# 2_unextended_ISO_matrix.net
KiCad netlist of a schematic drawn in Altium Designer
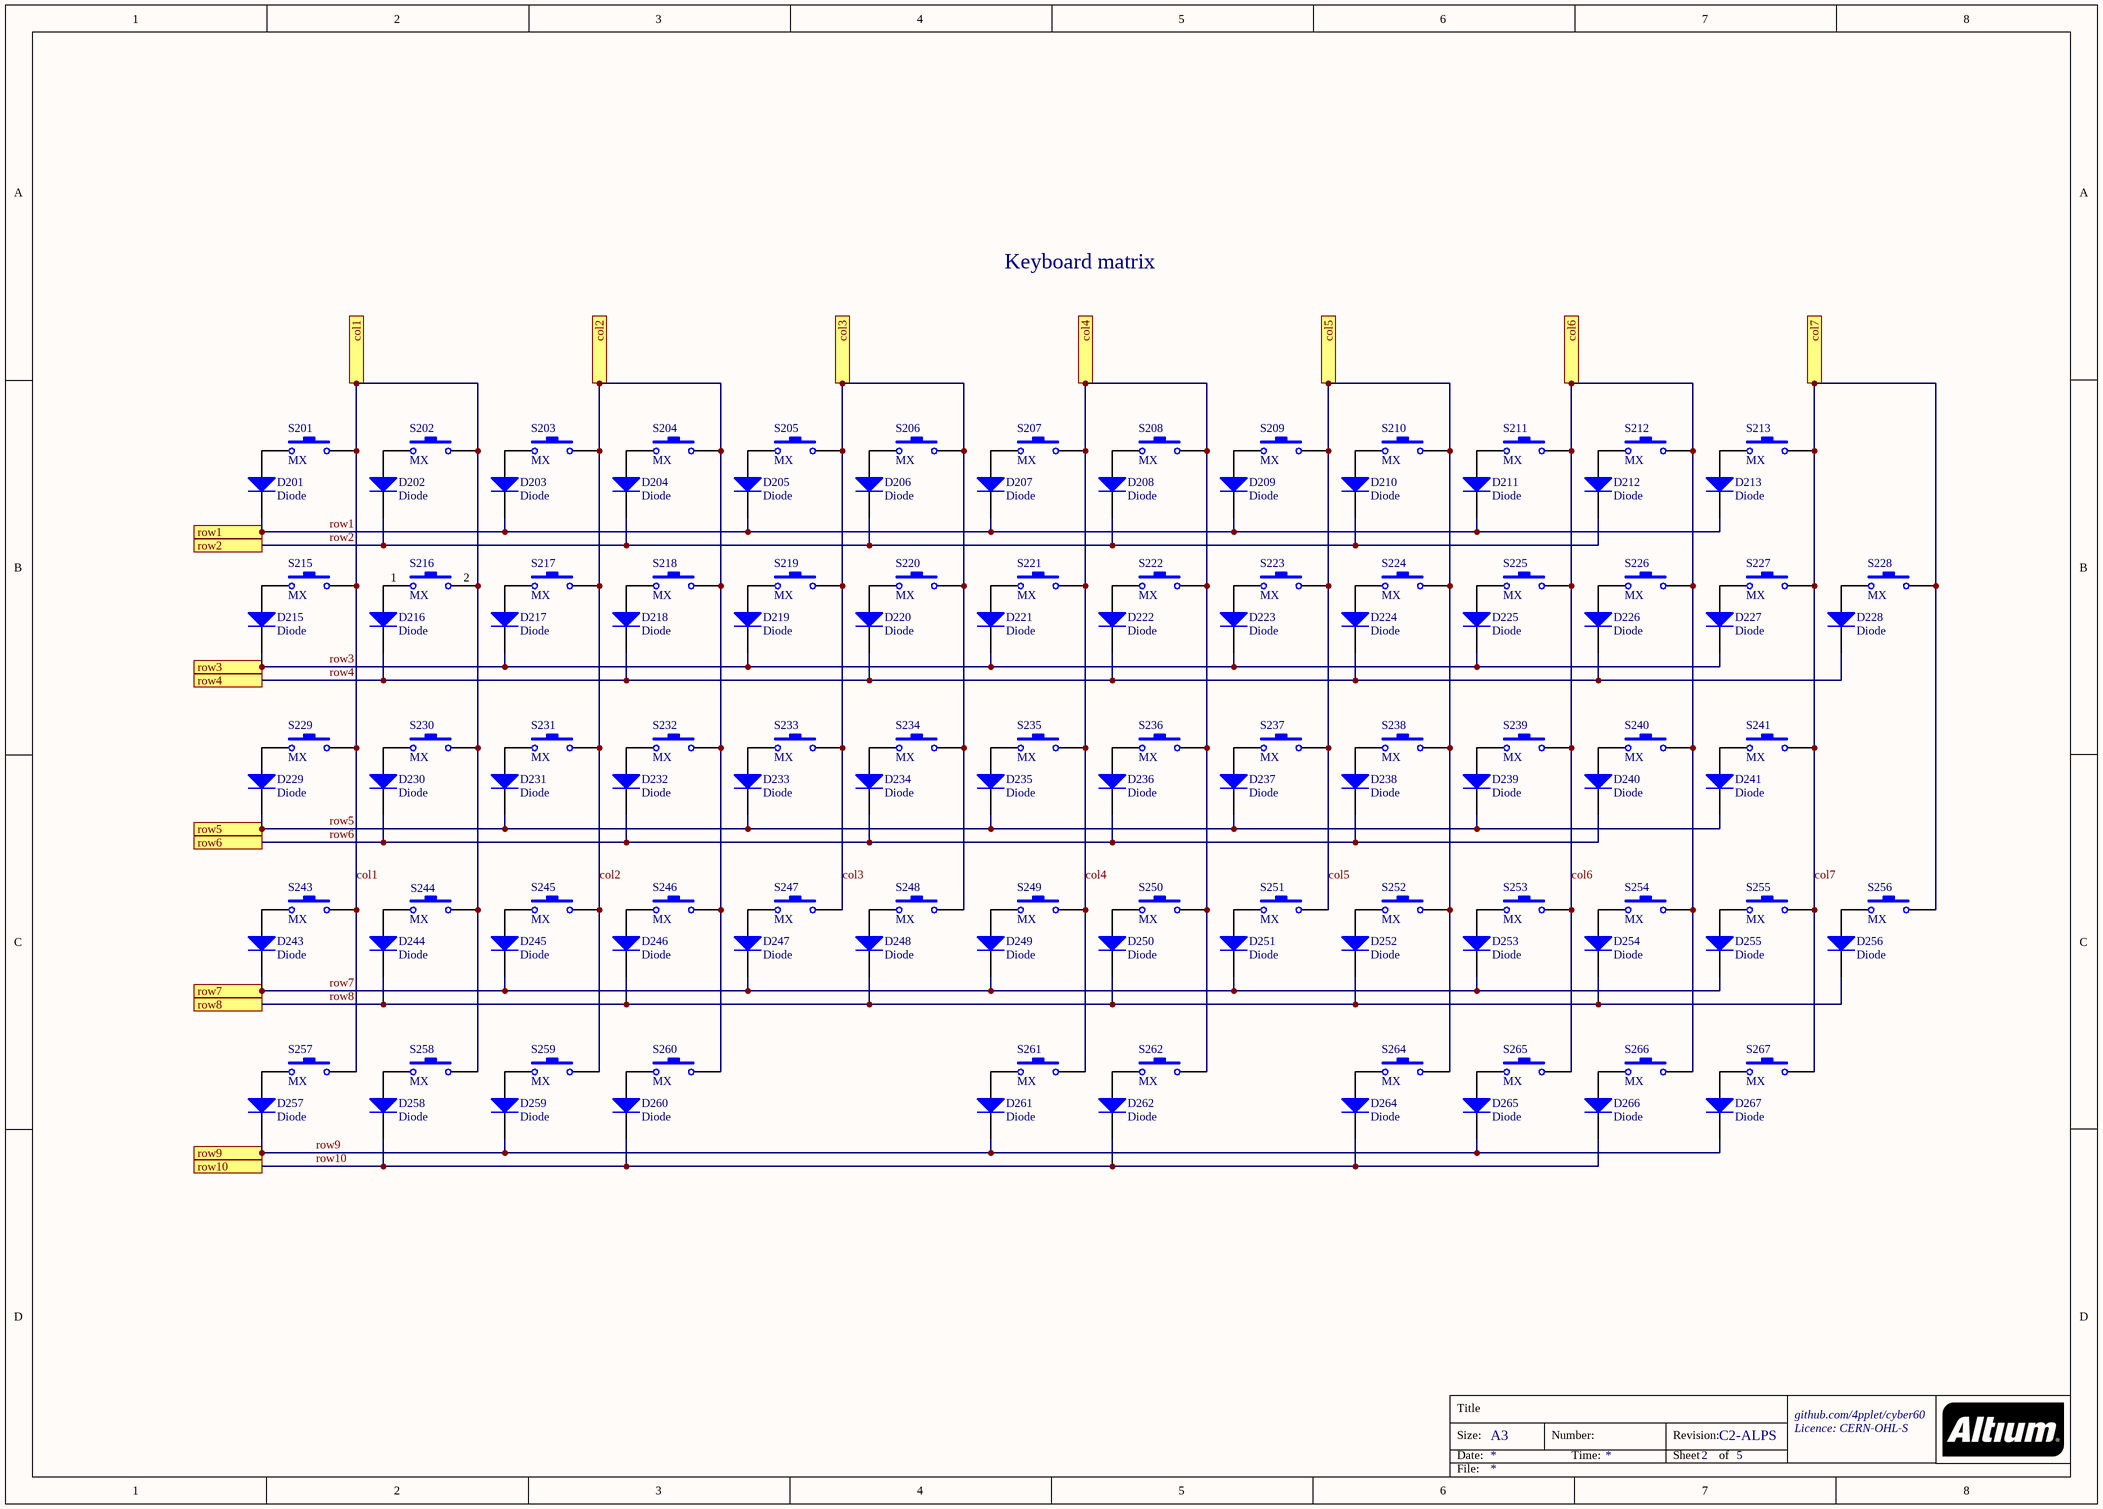
[diagram p0: 2_unextended_ISO_matrix.SchDoc]

(export (version "E")
  (design (tool "Eeschema 10.0.6"))
  (components
    (comp (ref "D201")
      (value "Diode")
      (footprint "SOD-123")
      (description "Default Diode")
      (fields (field (name "LCSC PART #") "C81598") (field (name "MRF.PART") "1N4148W"))
      (libsource (lib "Miscellaneous Devices") (part "Diode"))
    )
    (comp (ref "D202")
      (value "Diode")
      (footprint "SOD-123")
      (description "Default Diode")
      (fields (field (name "LCSC PART #") "C81598") (field (name "MRF.PART") "1N4148W"))
      (libsource (lib "Miscellaneous Devices") (part "Diode"))
    )
    (comp (ref "D203")
      (value "Diode")
      (footprint "SOD-123")
      (description "Default Diode")
      (fields (field (name "LCSC PART #") "C81598") (field (name "MRF.PART") "1N4148W"))
      (libsource (lib "Miscellaneous Devices") (part "Diode"))
    )
    (comp (ref "D204")
      (value "Diode")
      (footprint "SOD-123")
      (description "Default Diode")
      (fields (field (name "LCSC PART #") "C81598") (field (name "MRF.PART") "1N4148W"))
      (libsource (lib "Miscellaneous Devices") (part "Diode"))
    )
    (comp (ref "D205")
      (value "Diode")
      (footprint "SOD-123")
      (description "Default Diode")
      (fields (field (name "LCSC PART #") "C81598") (field (name "MRF.PART") "1N4148W"))
      (libsource (lib "Miscellaneous Devices") (part "Diode"))
    )
    (comp (ref "D206")
      (value "Diode")
      (footprint "SOD-123")
      (description "Default Diode")
      (fields (field (name "LCSC PART #") "C81598") (field (name "MRF.PART") "1N4148W"))
      (libsource (lib "Miscellaneous Devices") (part "Diode"))
    )
    (comp (ref "D207")
      (value "Diode")
      (footprint "SOD-123")
      (description "Default Diode")
      (fields (field (name "LCSC PART #") "C81598") (field (name "MRF.PART") "1N4148W"))
      (libsource (lib "Miscellaneous Devices") (part "Diode"))
    )
    (comp (ref "D208")
      (value "Diode")
      (footprint "SOD-123")
      (description "Default Diode")
      (fields (field (name "LCSC PART #") "C81598") (field (name "MRF.PART") "1N4148W"))
      (libsource (lib "Miscellaneous Devices") (part "Diode"))
    )
    (comp (ref "D209")
      (value "Diode")
      (footprint "SOD-123")
      (description "Default Diode")
      (fields (field (name "LCSC PART #") "C81598") (field (name "MRF.PART") "1N4148W"))
      (libsource (lib "Miscellaneous Devices") (part "Diode"))
    )
    (comp (ref "D210")
      (value "Diode")
      (footprint "SOD-123")
      (description "Default Diode")
      (fields (field (name "LCSC PART #") "C81598") (field (name "MRF.PART") "1N4148W"))
      (libsource (lib "Miscellaneous Devices") (part "Diode"))
    )
    (comp (ref "D211")
      (value "Diode")
      (footprint "SOD-123")
      (description "Default Diode")
      (fields (field (name "LCSC PART #") "C81598") (field (name "MRF.PART") "1N4148W"))
      (libsource (lib "Miscellaneous Devices") (part "Diode"))
    )
    (comp (ref "D212")
      (value "Diode")
      (footprint "SOD-123")
      (description "Default Diode")
      (fields (field (name "LCSC PART #") "C81598") (field (name "MRF.PART") "1N4148W"))
      (libsource (lib "Miscellaneous Devices") (part "Diode"))
    )
    (comp (ref "D213")
      (value "Diode")
      (footprint "SOD-123")
      (description "Default Diode")
      (fields (field (name "LCSC PART #") "C81598") (field (name "MRF.PART") "1N4148W"))
      (libsource (lib "Miscellaneous Devices") (part "Diode"))
    )
    (comp (ref "D215")
      (value "Diode")
      (footprint "SOD-123")
      (description "Default Diode")
      (fields (field (name "LCSC PART #") "C81598") (field (name "MRF.PART") "1N4148W"))
      (libsource (lib "Miscellaneous Devices") (part "Diode"))
    )
    (comp (ref "D216")
      (value "Diode")
      (footprint "SOD-123")
      (description "Default Diode")
      (fields (field (name "LCSC PART #") "C81598") (field (name "MRF.PART") "1N4148W"))
      (libsource (lib "Miscellaneous Devices") (part "Diode"))
    )
    (comp (ref "D217")
      (value "Diode")
      (footprint "SOD-123")
      (description "Default Diode")
      (fields (field (name "LCSC PART #") "C81598") (field (name "MRF.PART") "1N4148W"))
      (libsource (lib "Miscellaneous Devices") (part "Diode"))
    )
    (comp (ref "D218")
      (value "Diode")
      (footprint "SOD-123")
      (description "Default Diode")
      (fields (field (name "LCSC PART #") "C81598") (field (name "MRF.PART") "1N4148W"))
      (libsource (lib "Miscellaneous Devices") (part "Diode"))
    )
    (comp (ref "D219")
      (value "Diode")
      (footprint "SOD-123")
      (description "Default Diode")
      (fields (field (name "LCSC PART #") "C81598") (field (name "MRF.PART") "1N4148W"))
      (libsource (lib "Miscellaneous Devices") (part "Diode"))
    )
    (comp (ref "D220")
      (value "Diode")
      (footprint "SOD-123")
      (description "Default Diode")
      (fields (field (name "LCSC PART #") "C81598") (field (name "MRF.PART") "1N4148W"))
      (libsource (lib "Miscellaneous Devices") (part "Diode"))
    )
    (comp (ref "D221")
      (value "Diode")
      (footprint "SOD-123")
      (description "Default Diode")
      (fields (field (name "LCSC PART #") "C81598") (field (name "MRF.PART") "1N4148W"))
      (libsource (lib "Miscellaneous Devices") (part "Diode"))
    )
    (comp (ref "D222")
      (value "Diode")
      (footprint "SOD-123")
      (description "Default Diode")
      (fields (field (name "LCSC PART #") "C81598") (field (name "MRF.PART") "1N4148W"))
      (libsource (lib "Miscellaneous Devices") (part "Diode"))
    )
    (comp (ref "D223")
      (value "Diode")
      (footprint "SOD-123")
      (description "Default Diode")
      (fields (field (name "LCSC PART #") "C81598") (field (name "MRF.PART") "1N4148W"))
      (libsource (lib "Miscellaneous Devices") (part "Diode"))
    )
    (comp (ref "D224")
      (value "Diode")
      (footprint "SOD-123")
      (description "Default Diode")
      (fields (field (name "LCSC PART #") "C81598") (field (name "MRF.PART") "1N4148W"))
      (libsource (lib "Miscellaneous Devices") (part "Diode"))
    )
    (comp (ref "D225")
      (value "Diode")
      (footprint "SOD-123")
      (description "Default Diode")
      (fields (field (name "LCSC PART #") "C81598") (field (name "MRF.PART") "1N4148W"))
      (libsource (lib "Miscellaneous Devices") (part "Diode"))
    )
    (comp (ref "D226")
      (value "Diode")
      (footprint "SOD-123")
      (description "Default Diode")
      (fields (field (name "LCSC PART #") "C81598") (field (name "MRF.PART") "1N4148W"))
      (libsource (lib "Miscellaneous Devices") (part "Diode"))
    )
    (comp (ref "D227")
      (value "Diode")
      (footprint "SOD-123")
      (description "Default Diode")
      (fields (field (name "LCSC PART #") "C81598") (field (name "MRF.PART") "1N4148W"))
      (libsource (lib "Miscellaneous Devices") (part "Diode"))
    )
    (comp (ref "D228")
      (value "Diode")
      (footprint "SOD-123")
      (description "Default Diode")
      (fields (field (name "LCSC PART #") "C81598") (field (name "MRF.PART") "1N4148W"))
      (libsource (lib "Miscellaneous Devices") (part "Diode"))
    )
    (comp (ref "D229")
      (value "Diode")
      (footprint "SOD-123")
      (description "Default Diode")
      (fields (field (name "LCSC PART #") "C81598") (field (name "MRF.PART") "1N4148W"))
      (libsource (lib "Miscellaneous Devices") (part "Diode"))
    )
    (comp (ref "D230")
      (value "Diode")
      (footprint "SOD-123")
      (description "Default Diode")
      (fields (field (name "LCSC PART #") "C81598") (field (name "MRF.PART") "1N4148W"))
      (libsource (lib "Miscellaneous Devices") (part "Diode"))
    )
    (comp (ref "D231")
      (value "Diode")
      (footprint "SOD-123")
      (description "Default Diode")
      (fields (field (name "LCSC PART #") "C81598") (field (name "MRF.PART") "1N4148W"))
      (libsource (lib "Miscellaneous Devices") (part "Diode"))
    )
    (comp (ref "D232")
      (value "Diode")
      (footprint "SOD-123")
      (description "Default Diode")
      (fields (field (name "LCSC PART #") "C81598") (field (name "MRF.PART") "1N4148W"))
      (libsource (lib "Miscellaneous Devices") (part "Diode"))
    )
    (comp (ref "D233")
      (value "Diode")
      (footprint "SOD-123")
      (description "Default Diode")
      (fields (field (name "LCSC PART #") "C81598") (field (name "MRF.PART") "1N4148W"))
      (libsource (lib "Miscellaneous Devices") (part "Diode"))
    )
    (comp (ref "D234")
      (value "Diode")
      (footprint "SOD-123")
      (description "Default Diode")
      (fields (field (name "LCSC PART #") "C81598") (field (name "MRF.PART") "1N4148W"))
      (libsource (lib "Miscellaneous Devices") (part "Diode"))
    )
    (comp (ref "D235")
      (value "Diode")
      (footprint "SOD-123")
      (description "Default Diode")
      (fields (field (name "LCSC PART #") "C81598") (field (name "MRF.PART") "1N4148W"))
      (libsource (lib "Miscellaneous Devices") (part "Diode"))
    )
    (comp (ref "D236")
      (value "Diode")
      (footprint "SOD-123")
      (description "Default Diode")
      (fields (field (name "LCSC PART #") "C81598") (field (name "MRF.PART") "1N4148W"))
      (libsource (lib "Miscellaneous Devices") (part "Diode"))
    )
    (comp (ref "D237")
      (value "Diode")
      (footprint "SOD-123")
      (description "Default Diode")
      (fields (field (name "LCSC PART #") "C81598") (field (name "MRF.PART") "1N4148W"))
      (libsource (lib "Miscellaneous Devices") (part "Diode"))
    )
    (comp (ref "D238")
      (value "Diode")
      (footprint "SOD-123")
      (description "Default Diode")
      (fields (field (name "LCSC PART #") "C81598") (field (name "MRF.PART") "1N4148W"))
      (libsource (lib "Miscellaneous Devices") (part "Diode"))
    )
    (comp (ref "D239")
      (value "Diode")
      (footprint "SOD-123")
      (description "Default Diode")
      (fields (field (name "LCSC PART #") "C81598") (field (name "MRF.PART") "1N4148W"))
      (libsource (lib "Miscellaneous Devices") (part "Diode"))
    )
    (comp (ref "D240")
      (value "Diode")
      (footprint "SOD-123")
      (description "Default Diode")
      (fields (field (name "LCSC PART #") "C81598") (field (name "MRF.PART") "1N4148W"))
      (libsource (lib "Miscellaneous Devices") (part "Diode"))
    )
    (comp (ref "D241")
      (value "Diode")
      (footprint "SOD-123")
      (description "Default Diode")
      (fields (field (name "LCSC PART #") "C81598") (field (name "MRF.PART") "1N4148W"))
      (libsource (lib "Miscellaneous Devices") (part "Diode"))
    )
    (comp (ref "D243")
      (value "Diode")
      (footprint "SOD-123")
      (description "Default Diode")
      (fields (field (name "LCSC PART #") "C81598") (field (name "MRF.PART") "1N4148W"))
      (libsource (lib "Miscellaneous Devices") (part "Diode"))
    )
    (comp (ref "D244")
      (value "Diode")
      (footprint "SOD-123")
      (description "Default Diode")
      (fields (field (name "LCSC PART #") "C81598") (field (name "MRF.PART") "1N4148W"))
      (libsource (lib "Miscellaneous Devices") (part "Diode"))
    )
    (comp (ref "D245")
      (value "Diode")
      (footprint "SOD-123")
      (description "Default Diode")
      (fields (field (name "LCSC PART #") "C81598") (field (name "MRF.PART") "1N4148W"))
      (libsource (lib "Miscellaneous Devices") (part "Diode"))
    )
    (comp (ref "D246")
      (value "Diode")
      (footprint "SOD-123")
      (description "Default Diode")
      (fields (field (name "LCSC PART #") "C81598") (field (name "MRF.PART") "1N4148W"))
      (libsource (lib "Miscellaneous Devices") (part "Diode"))
    )
    (comp (ref "D247")
      (value "Diode")
      (footprint "SOD-123")
      (description "Default Diode")
      (fields (field (name "LCSC PART #") "C81598") (field (name "MRF.PART") "1N4148W"))
      (libsource (lib "Miscellaneous Devices") (part "Diode"))
    )
    (comp (ref "D248")
      (value "Diode")
      (footprint "SOD-123")
      (description "Default Diode")
      (fields (field (name "LCSC PART #") "C81598") (field (name "MRF.PART") "1N4148W"))
      (libsource (lib "Miscellaneous Devices") (part "Diode"))
    )
    (comp (ref "D249")
      (value "Diode")
      (footprint "SOD-123")
      (description "Default Diode")
      (fields (field (name "LCSC PART #") "C81598") (field (name "MRF.PART") "1N4148W"))
      (libsource (lib "Miscellaneous Devices") (part "Diode"))
    )
    (comp (ref "D250")
      (value "Diode")
      (footprint "SOD-123")
      (description "Default Diode")
      (fields (field (name "LCSC PART #") "C81598") (field (name "MRF.PART") "1N4148W"))
      (libsource (lib "Miscellaneous Devices") (part "Diode"))
    )
    (comp (ref "D251")
      (value "Diode")
      (footprint "SOD-123")
      (description "Default Diode")
      (fields (field (name "LCSC PART #") "C81598") (field (name "MRF.PART") "1N4148W"))
      (libsource (lib "Miscellaneous Devices") (part "Diode"))
    )
    (comp (ref "D252")
      (value "Diode")
      (footprint "SOD-123")
      (description "Default Diode")
      (fields (field (name "LCSC PART #") "C81598") (field (name "MRF.PART") "1N4148W"))
      (libsource (lib "Miscellaneous Devices") (part "Diode"))
    )
    (comp (ref "D253")
      (value "Diode")
      (footprint "SOD-123")
      (description "Default Diode")
      (fields (field (name "LCSC PART #") "C81598") (field (name "MRF.PART") "1N4148W"))
      (libsource (lib "Miscellaneous Devices") (part "Diode"))
    )
    (comp (ref "D254")
      (value "Diode")
      (footprint "SOD-123")
      (description "Default Diode")
      (fields (field (name "LCSC PART #") "C81598") (field (name "MRF.PART") "1N4148W"))
      (libsource (lib "Miscellaneous Devices") (part "Diode"))
    )
    (comp (ref "D255")
      (value "Diode")
      (footprint "SOD-123")
      (description "Default Diode")
      (fields (field (name "LCSC PART #") "C81598") (field (name "MRF.PART") "1N4148W"))
      (libsource (lib "Miscellaneous Devices") (part "Diode"))
    )
    (comp (ref "D256")
      (value "Diode")
      (footprint "SOD-123")
      (description "Default Diode")
      (fields (field (name "LCSC PART #") "C81598") (field (name "MRF.PART") "1N4148W"))
      (libsource (lib "Miscellaneous Devices") (part "Diode"))
    )
    (comp (ref "D257")
      (value "Diode")
      (footprint "SOD-123")
      (description "Default Diode")
      (fields (field (name "LCSC PART #") "C81598") (field (name "MRF.PART") "1N4148W"))
      (libsource (lib "Miscellaneous Devices") (part "Diode"))
    )
    (comp (ref "D258")
      (value "Diode")
      (footprint "SOD-123")
      (description "Default Diode")
      (fields (field (name "LCSC PART #") "C81598") (field (name "MRF.PART") "1N4148W"))
      (libsource (lib "Miscellaneous Devices") (part "Diode"))
    )
    (comp (ref "D259")
      (value "Diode")
      (footprint "SOD-123")
      (description "Default Diode")
      (fields (field (name "LCSC PART #") "C81598") (field (name "MRF.PART") "1N4148W"))
      (libsource (lib "Miscellaneous Devices") (part "Diode"))
    )
    (comp (ref "D260")
      (value "Diode")
      (footprint "SOD-123")
      (description "Default Diode")
      (fields (field (name "LCSC PART #") "C81598") (field (name "MRF.PART") "1N4148W"))
      (libsource (lib "Miscellaneous Devices") (part "Diode"))
    )
    (comp (ref "D261")
      (value "Diode")
      (footprint "SOD-123")
      (description "Default Diode")
      (fields (field (name "LCSC PART #") "C81598") (field (name "MRF.PART") "1N4148W"))
      (libsource (lib "Miscellaneous Devices") (part "Diode"))
    )
    (comp (ref "D262")
      (value "Diode")
      (footprint "SOD-123")
      (description "Default Diode")
      (fields (field (name "LCSC PART #") "C81598") (field (name "MRF.PART") "1N4148W"))
      (libsource (lib "Miscellaneous Devices") (part "Diode"))
    )
    (comp (ref "D264")
      (value "Diode")
      (footprint "SOD-123")
      (description "Default Diode")
      (fields (field (name "LCSC PART #") "C81598") (field (name "MRF.PART") "1N4148W"))
      (libsource (lib "Miscellaneous Devices") (part "Diode"))
    )
    (comp (ref "D265")
      (value "Diode")
      (footprint "SOD-123")
      (description "Default Diode")
      (fields (field (name "LCSC PART #") "C81598") (field (name "MRF.PART") "1N4148W"))
      (libsource (lib "Miscellaneous Devices") (part "Diode"))
    )
    (comp (ref "D266")
      (value "Diode")
      (footprint "SOD-123")
      (description "Default Diode")
      (fields (field (name "LCSC PART #") "C81598") (field (name "MRF.PART") "1N4148W"))
      (libsource (lib "Miscellaneous Devices") (part "Diode"))
    )
    (comp (ref "D267")
      (value "Diode")
      (footprint "SOD-123")
      (description "Default Diode")
      (fields (field (name "LCSC PART #") "C81598") (field (name "MRF.PART") "1N4148W"))
      (libsource (lib "Miscellaneous Devices") (part "Diode"))
    )
    (comp (ref "S201")
      (value "MX")
      (footprint "Alps-switch - switched pol")
      (description "Switch")
      (libsource (lib "Miscellaneous Devices") (part "SW-PB"))
    )
    (comp (ref "S202")
      (value "MX")
      (footprint "Alps-switch - switched pol")
      (description "Switch")
      (libsource (lib "Miscellaneous Devices") (part "SW-PB"))
    )
    (comp (ref "S203")
      (value "MX")
      (footprint "Alps-switch - switched pol")
      (description "Switch")
      (libsource (lib "Miscellaneous Devices") (part "SW-PB"))
    )
    (comp (ref "S204")
      (value "MX")
      (footprint "Alps-switch - switched pol")
      (description "Switch")
      (libsource (lib "Miscellaneous Devices") (part "SW-PB"))
    )
    (comp (ref "S205")
      (value "MX")
      (footprint "Alps-switch - switched pol")
      (description "Switch")
      (libsource (lib "Miscellaneous Devices") (part "SW-PB"))
    )
    (comp (ref "S206")
      (value "MX")
      (footprint "Alps-switch - switched pol")
      (description "Switch")
      (libsource (lib "Miscellaneous Devices") (part "SW-PB"))
    )
    (comp (ref "S207")
      (value "MX")
      (footprint "Alps-switch - switched pol")
      (description "Switch")
      (libsource (lib "Miscellaneous Devices") (part "SW-PB"))
    )
    (comp (ref "S208")
      (value "MX")
      (footprint "Alps-switch - switched pol")
      (description "Switch")
      (libsource (lib "Miscellaneous Devices") (part "SW-PB"))
    )
    (comp (ref "S209")
      (value "MX")
      (footprint "Alps-switch - switched pol")
      (description "Switch")
      (libsource (lib "Miscellaneous Devices") (part "SW-PB"))
    )
    (comp (ref "S210")
      (value "MX")
      (footprint "Alps-switch - switched pol")
      (description "Switch")
      (libsource (lib "Miscellaneous Devices") (part "SW-PB"))
    )
    (comp (ref "S211")
      (value "MX")
      (footprint "Alps-switch - switched pol")
      (description "Switch")
      (libsource (lib "Miscellaneous Devices") (part "SW-PB"))
    )
    (comp (ref "S212")
      (value "MX")
      (footprint "Alps-switch - switched pol")
      (description "Switch")
      (libsource (lib "Miscellaneous Devices") (part "SW-PB"))
    )
    (comp (ref "S213")
      (value "MX")
      (footprint "Alps-switch")
      (description "Switch")
      (libsource (lib "Miscellaneous Devices") (part "SW-PB"))
    )
    (comp (ref "S215")
      (value "MX")
      (footprint "Alps-switch - switched pol")
      (description "TAB")
      (libsource (lib "Miscellaneous Devices") (part "SW-PB"))
    )
    (comp (ref "S216")
      (value "MX")
      (footprint "Alps-switch - switched pol")
      (description "Switch")
      (libsource (lib "") (part "SW-PB_1"))
    )
    (comp (ref "S217")
      (value "MX")
      (footprint "Alps-switch - switched pol")
      (description "Switch")
      (libsource (lib "Miscellaneous Devices") (part "SW-PB"))
    )
    (comp (ref "S218")
      (value "MX")
      (footprint "Alps-switch - switched pol")
      (description "Switch")
      (libsource (lib "Miscellaneous Devices") (part "SW-PB"))
    )
    (comp (ref "S219")
      (value "MX")
      (footprint "Alps-switch - switched pol")
      (description "Switch")
      (libsource (lib "Miscellaneous Devices") (part "SW-PB"))
    )
    (comp (ref "S220")
      (value "MX")
      (footprint "Alps-switch - switched pol")
      (description "Switch")
      (libsource (lib "Miscellaneous Devices") (part "SW-PB"))
    )
    (comp (ref "S221")
      (value "MX")
      (footprint "Alps-switch - switched pol")
      (description "Switch")
      (libsource (lib "Miscellaneous Devices") (part "SW-PB"))
    )
    (comp (ref "S222")
      (value "MX")
      (footprint "Alps-switch - switched pol")
      (description "Switch")
      (libsource (lib "Miscellaneous Devices") (part "SW-PB"))
    )
    (comp (ref "S223")
      (value "MX")
      (footprint "Alps-switch - switched pol")
      (description "Switch")
      (libsource (lib "Miscellaneous Devices") (part "SW-PB"))
    )
    (comp (ref "S224")
      (value "MX")
      (footprint "Alps-switch - switched pol")
      (description "Switch")
      (libsource (lib "Miscellaneous Devices") (part "SW-PB"))
    )
    (comp (ref "S225")
      (value "MX")
      (footprint "Alps-switch - switched pol")
      (description "Switch")
      (libsource (lib "Miscellaneous Devices") (part "SW-PB"))
    )
    (comp (ref "S226")
      (value "MX")
      (footprint "Alps-switch")
      (description "Switch")
      (libsource (lib "Miscellaneous Devices") (part "SW-PB"))
    )
    (comp (ref "S227")
      (value "MX")
      (footprint "Alps-switch")
      (description "Switch")
      (libsource (lib "Miscellaneous Devices") (part "SW-PB"))
    )
    (comp (ref "S228")
      (value "MX")
      (footprint "Alps-switch - switched pol")
      (description "Switch")
      (libsource (lib "Miscellaneous Devices") (part "SW-PB"))
    )
    (comp (ref "S229")
      (value "MX")
      (footprint "Alps-switch")
      (description "Switch")
      (libsource (lib "Miscellaneous Devices") (part "SW-PB"))
    )
    (comp (ref "S230")
      (value "MX")
      (footprint "Alps-switch - switched pol")
      (description "Switch")
      (libsource (lib "Miscellaneous Devices") (part "SW-PB"))
    )
    (comp (ref "S231")
      (value "MX")
      (footprint "Alps-switch - switched pol")
      (description "Switch")
      (libsource (lib "Miscellaneous Devices") (part "SW-PB"))
    )
    (comp (ref "S232")
      (value "MX")
      (footprint "Alps-switch - switched pol")
      (description "Switch")
      (libsource (lib "Miscellaneous Devices") (part "SW-PB"))
    )
    (comp (ref "S233")
      (value "MX")
      (footprint "Alps-switch - switched pol")
      (description "Switch")
      (libsource (lib "Miscellaneous Devices") (part "SW-PB"))
    )
    (comp (ref "S234")
      (value "MX")
      (footprint "Alps-switch - switched pol")
      (description "Switch")
      (libsource (lib "Miscellaneous Devices") (part "SW-PB"))
    )
    (comp (ref "S235")
      (value "MX")
      (footprint "Alps-switch - switched pol")
      (description "Switch")
      (libsource (lib "Miscellaneous Devices") (part "SW-PB"))
    )
    (comp (ref "S236")
      (value "MX")
      (footprint "Alps-switch - switched pol")
      (description "Switch")
      (libsource (lib "Miscellaneous Devices") (part "SW-PB"))
    )
    (comp (ref "S237")
      (value "MX")
      (footprint "Alps-switch - switched pol")
      (description "Switch")
      (libsource (lib "Miscellaneous Devices") (part "SW-PB"))
    )
    (comp (ref "S238")
      (value "MX")
      (footprint "Alps-switch - switched pol")
      (description "Switch")
      (libsource (lib "Miscellaneous Devices") (part "SW-PB"))
    )
    (comp (ref "S239")
      (value "MX")
      (footprint "Alps-switch")
      (description "Switch")
      (libsource (lib "Miscellaneous Devices") (part "SW-PB"))
    )
    (comp (ref "S240")
      (value "MX")
      (footprint "Alps-switch - switched pol")
      (description "Switch")
      (libsource (lib "Miscellaneous Devices") (part "SW-PB"))
    )
    (comp (ref "S241")
      (value "MX")
      (footprint "Alps-switch - switched pol")
      (description "Switch")
      (libsource (lib "Miscellaneous Devices") (part "SW-PB"))
    )
    (comp (ref "S243")
      (value "MX")
      (footprint "Alps-switch - switched pol")
      (description "Switch")
      (libsource (lib "Miscellaneous Devices") (part "SW-PB"))
    )
    (comp (ref "S244")
      (value "MX")
      (footprint "Alps-switch - switched pol")
      (description "Switch")
      (libsource (lib "Miscellaneous Devices") (part "SW-PB"))
    )
    (comp (ref "S245")
      (value "MX")
      (footprint "Alps-switch - switched pol")
      (description "Switch")
      (libsource (lib "Miscellaneous Devices") (part "SW-PB"))
    )
    (comp (ref "S246")
      (value "MX")
      (footprint "Alps-switch - switched pol")
      (description "Switch")
      (libsource (lib "Miscellaneous Devices") (part "SW-PB"))
    )
    (comp (ref "S247")
      (value "MX")
      (footprint "Alps-switch - switched pol")
      (description "Switch")
      (libsource (lib "Miscellaneous Devices") (part "SW-PB"))
    )
    (comp (ref "S248")
      (value "MX")
      (footprint "Alps-switch - switched pol")
      (description "Switch")
      (libsource (lib "Miscellaneous Devices") (part "SW-PB"))
    )
    (comp (ref "S249")
      (value "MX")
      (footprint "Alps-switch - switched pol")
      (description "Switch")
      (libsource (lib "Miscellaneous Devices") (part "SW-PB"))
    )
    (comp (ref "S250")
      (value "MX")
      (footprint "Alps-switch - switched pol")
      (description "Switch")
      (libsource (lib "Miscellaneous Devices") (part "SW-PB"))
    )
    (comp (ref "S251")
      (value "MX")
      (footprint "Alps-switch - switched pol")
      (description "Switch")
      (libsource (lib "Miscellaneous Devices") (part "SW-PB"))
    )
    (comp (ref "S252")
      (value "MX")
      (footprint "Alps-switch - switched pol")
      (description "Switch")
      (libsource (lib "Miscellaneous Devices") (part "SW-PB"))
    )
    (comp (ref "S253")
      (value "MX")
      (footprint "Alps-switch - switched pol")
      (description "Switch")
      (libsource (lib "Miscellaneous Devices") (part "SW-PB"))
    )
    (comp (ref "S254")
      (value "MX")
      (footprint "Alps-switch - switched pol")
      (description "Switch")
      (libsource (lib "Miscellaneous Devices") (part "SW-PB"))
    )
    (comp (ref "S255")
      (value "MX")
      (footprint "Alps-switch")
      (description "Switch")
      (libsource (lib "Miscellaneous Devices") (part "SW-PB"))
    )
    (comp (ref "S256")
      (value "MX")
      (footprint "Alps-switch")
      (description "Switch")
      (libsource (lib "Miscellaneous Devices") (part "SW-PB"))
    )
    (comp (ref "S257")
      (value "MX")
      (footprint "Alps-switch - switched pol")
      (description "Switch")
      (libsource (lib "Miscellaneous Devices") (part "SW-PB"))
    )
    (comp (ref "S258")
      (value "MX")
      (footprint "Alps-switch")
      (description "Switch")
      (libsource (lib "Miscellaneous Devices") (part "SW-PB"))
    )
    (comp (ref "S259")
      (value "MX")
      (footprint "Alps-switch")
      (description "Switch")
      (libsource (lib "Miscellaneous Devices") (part "SW-PB"))
    )
    (comp (ref "S260")
      (value "MX")
      (footprint "Alps-switch")
      (description "Switch")
      (libsource (lib "Miscellaneous Devices") (part "SW-PB"))
    )
    (comp (ref "S261")
      (value "MX")
      (footprint "Alps-switch - switched pol")
      (description "Switch")
      (libsource (lib "Miscellaneous Devices") (part "SW-PB"))
    )
    (comp (ref "S262")
      (value "MX")
      (footprint "Alps-switch - switched pol")
      (description "Switch")
      (libsource (lib "Miscellaneous Devices") (part "SW-PB"))
    )
    (comp (ref "S264")
      (value "MX")
      (footprint "Alps-switch")
      (description "Switch")
      (libsource (lib "Miscellaneous Devices") (part "SW-PB"))
    )
    (comp (ref "S265")
      (value "MX")
      (footprint "Alps-switch")
      (description "Switch")
      (libsource (lib "Miscellaneous Devices") (part "SW-PB"))
    )
    (comp (ref "S266")
      (value "MX")
      (footprint "Alps-switch")
      (description "Switch")
      (libsource (lib "Miscellaneous Devices") (part "SW-PB"))
    )
    (comp (ref "S267")
      (value "MX")
      (footprint "ALPS-switch - AEKISO r_shift")
      (description "Switch")
      (libsource (lib "Miscellaneous Devices") (part "SW-PB"))
    )
  )
  (nets
    (net (code "1") (name "/col1") (class "Default")
      (node (ref "S201") (pin "2") (pinfunction "2_2") (pintype "passive"))
      (node (ref "S202") (pin "2") (pinfunction "2_2") (pintype "passive"))
      (node (ref "S215") (pin "2") (pinfunction "2_2") (pintype "passive"))
      (node (ref "S216") (pin "2") (pinfunction "2_2") (pintype "passive"))
      (node (ref "S229") (pin "2") (pinfunction "2_2") (pintype "passive"))
      (node (ref "S230") (pin "2") (pinfunction "2_2") (pintype "passive"))
      (node (ref "S243") (pin "2") (pinfunction "2_2") (pintype "passive"))
      (node (ref "S244") (pin "2") (pinfunction "2_2") (pintype "passive"))
      (node (ref "S257") (pin "2") (pinfunction "2_2") (pintype "passive"))
      (node (ref "S258") (pin "2") (pinfunction "2_2") (pintype "passive"))
    )
    (net (code "2") (name "/col2") (class "Default")
      (node (ref "S203") (pin "2") (pinfunction "2_2") (pintype "passive"))
      (node (ref "S204") (pin "2") (pinfunction "2_2") (pintype "passive"))
      (node (ref "S217") (pin "2") (pinfunction "2_2") (pintype "passive"))
      (node (ref "S218") (pin "2") (pinfunction "2_2") (pintype "passive"))
      (node (ref "S231") (pin "2") (pinfunction "2_2") (pintype "passive"))
      (node (ref "S232") (pin "2") (pinfunction "2_2") (pintype "passive"))
      (node (ref "S245") (pin "2") (pinfunction "2_2") (pintype "passive"))
      (node (ref "S246") (pin "2") (pinfunction "2_2") (pintype "passive"))
      (node (ref "S259") (pin "2") (pinfunction "2_2") (pintype "passive"))
      (node (ref "S260") (pin "2") (pinfunction "2_2") (pintype "passive"))
    )
    (net (code "3") (name "/col3") (class "Default")
      (node (ref "S205") (pin "2") (pinfunction "2_2") (pintype "passive"))
      (node (ref "S206") (pin "2") (pinfunction "2_2") (pintype "passive"))
      (node (ref "S219") (pin "2") (pinfunction "2_2") (pintype "passive"))
      (node (ref "S220") (pin "2") (pinfunction "2_2") (pintype "passive"))
      (node (ref "S233") (pin "2") (pinfunction "2_2") (pintype "passive"))
      (node (ref "S234") (pin "2") (pinfunction "2_2") (pintype "passive"))
      (node (ref "S247") (pin "2") (pinfunction "2_2") (pintype "passive"))
      (node (ref "S248") (pin "2") (pinfunction "2_2") (pintype "passive"))
    )
    (net (code "4") (name "/col4") (class "Default")
      (node (ref "S207") (pin "2") (pinfunction "2_2") (pintype "passive"))
      (node (ref "S208") (pin "2") (pinfunction "2_2") (pintype "passive"))
      (node (ref "S221") (pin "2") (pinfunction "2_2") (pintype "passive"))
      (node (ref "S222") (pin "2") (pinfunction "2_2") (pintype "passive"))
      (node (ref "S235") (pin "2") (pinfunction "2_2") (pintype "passive"))
      (node (ref "S236") (pin "2") (pinfunction "2_2") (pintype "passive"))
      (node (ref "S249") (pin "2") (pinfunction "2_2") (pintype "passive"))
      (node (ref "S250") (pin "2") (pinfunction "2_2") (pintype "passive"))
      (node (ref "S261") (pin "1") (pinfunction "1_1") (pintype "passive"))
      (node (ref "S262") (pin "2") (pinfunction "2_2") (pintype "passive"))
    )
    (net (code "5") (name "/col5") (class "Default")
      (node (ref "S209") (pin "2") (pinfunction "2_2") (pintype "passive"))
      (node (ref "S210") (pin "2") (pinfunction "2_2") (pintype "passive"))
      (node (ref "S223") (pin "2") (pinfunction "2_2") (pintype "passive"))
      (node (ref "S224") (pin "2") (pinfunction "2_2") (pintype "passive"))
      (node (ref "S237") (pin "2") (pinfunction "2_2") (pintype "passive"))
      (node (ref "S238") (pin "2") (pinfunction "2_2") (pintype "passive"))
      (node (ref "S251") (pin "2") (pinfunction "2_2") (pintype "passive"))
      (node (ref "S252") (pin "2") (pinfunction "2_2") (pintype "passive"))
      (node (ref "S264") (pin "1") (pinfunction "1_1") (pintype "passive"))
    )
    (net (code "6") (name "/col6") (class "Default")
      (node (ref "S211") (pin "2") (pinfunction "2_2") (pintype "passive"))
      (node (ref "S212") (pin "2") (pinfunction "2_2") (pintype "passive"))
      (node (ref "S225") (pin "2") (pinfunction "2_2") (pintype "passive"))
      (node (ref "S226") (pin "2") (pinfunction "2_2") (pintype "passive"))
      (node (ref "S239") (pin "2") (pinfunction "2_2") (pintype "passive"))
      (node (ref "S240") (pin "2") (pinfunction "2_2") (pintype "passive"))
      (node (ref "S253") (pin "2") (pinfunction "2_2") (pintype "passive"))
      (node (ref "S254") (pin "2") (pinfunction "2_2") (pintype "passive"))
      (node (ref "S265") (pin "2") (pinfunction "2_2") (pintype "passive"))
      (node (ref "S266") (pin "2") (pinfunction "2_2") (pintype "passive"))
    )
    (net (code "7") (name "/col7") (class "Default")
      (node (ref "S213") (pin "2") (pinfunction "2_2") (pintype "passive"))
      (node (ref "S227") (pin "2") (pinfunction "2_2") (pintype "passive"))
      (node (ref "S228") (pin "1") (pinfunction "1_1") (pintype "passive"))
      (node (ref "S241") (pin "2") (pinfunction "2_2") (pintype "passive"))
      (node (ref "S255") (pin "2") (pinfunction "2_2") (pintype "passive"))
      (node (ref "S256") (pin "2") (pinfunction "2_2") (pintype "passive"))
      (node (ref "S267") (pin "1") (pinfunction "1_1") (pintype "passive"))
    )
    (net (code "8") (name "/row1") (class "Default")
      (node (ref "D201") (pin "2") (pinfunction "K_2") (pintype "passive"))
      (node (ref "D203") (pin "2") (pinfunction "K_2") (pintype "passive"))
      (node (ref "D205") (pin "2") (pinfunction "K_2") (pintype "passive"))
      (node (ref "D207") (pin "2") (pinfunction "K_2") (pintype "passive"))
      (node (ref "D209") (pin "2") (pinfunction "K_2") (pintype "passive"))
      (node (ref "D211") (pin "2") (pinfunction "K_2") (pintype "passive"))
      (node (ref "D213") (pin "2") (pinfunction "K_2") (pintype "passive"))
    )
    (net (code "9") (name "/row2") (class "Default")
      (node (ref "D202") (pin "2") (pinfunction "K_2") (pintype "passive"))
      (node (ref "D204") (pin "2") (pinfunction "K_2") (pintype "passive"))
      (node (ref "D206") (pin "2") (pinfunction "K_2") (pintype "passive"))
      (node (ref "D208") (pin "2") (pinfunction "K_2") (pintype "passive"))
      (node (ref "D210") (pin "2") (pinfunction "K_2") (pintype "passive"))
      (node (ref "D212") (pin "2") (pinfunction "K_2") (pintype "passive"))
    )
    (net (code "10") (name "/row3") (class "Default")
      (node (ref "D215") (pin "2") (pinfunction "K_2") (pintype "passive"))
      (node (ref "D217") (pin "2") (pinfunction "K_2") (pintype "passive"))
      (node (ref "D219") (pin "2") (pinfunction "K_2") (pintype "passive"))
      (node (ref "D221") (pin "2") (pinfunction "K_2") (pintype "passive"))
      (node (ref "D223") (pin "2") (pinfunction "K_2") (pintype "passive"))
      (node (ref "D225") (pin "2") (pinfunction "K_2") (pintype "passive"))
      (node (ref "D227") (pin "2") (pinfunction "K_2") (pintype "passive"))
    )
    (net (code "11") (name "/row4") (class "Default")
      (node (ref "D216") (pin "2") (pinfunction "K_2") (pintype "passive"))
      (node (ref "D218") (pin "2") (pinfunction "K_2") (pintype "passive"))
      (node (ref "D220") (pin "2") (pinfunction "K_2") (pintype "passive"))
      (node (ref "D222") (pin "2") (pinfunction "K_2") (pintype "passive"))
      (node (ref "D224") (pin "2") (pinfunction "K_2") (pintype "passive"))
      (node (ref "D226") (pin "2") (pinfunction "K_2") (pintype "passive"))
      (node (ref "D228") (pin "2") (pinfunction "K_2") (pintype "passive"))
    )
    (net (code "12") (name "/row5") (class "Default")
      (node (ref "D229") (pin "2") (pinfunction "K_2") (pintype "passive"))
      (node (ref "D231") (pin "2") (pinfunction "K_2") (pintype "passive"))
      (node (ref "D233") (pin "2") (pinfunction "K_2") (pintype "passive"))
      (node (ref "D235") (pin "2") (pinfunction "K_2") (pintype "passive"))
      (node (ref "D237") (pin "2") (pinfunction "K_2") (pintype "passive"))
      (node (ref "D239") (pin "2") (pinfunction "K_2") (pintype "passive"))
      (node (ref "D241") (pin "2") (pinfunction "K_2") (pintype "passive"))
    )
    (net (code "13") (name "/row6") (class "Default")
      (node (ref "D230") (pin "2") (pinfunction "K_2") (pintype "passive"))
      (node (ref "D232") (pin "2") (pinfunction "K_2") (pintype "passive"))
      (node (ref "D234") (pin "2") (pinfunction "K_2") (pintype "passive"))
      (node (ref "D236") (pin "2") (pinfunction "K_2") (pintype "passive"))
      (node (ref "D238") (pin "2") (pinfunction "K_2") (pintype "passive"))
      (node (ref "D240") (pin "2") (pinfunction "K_2") (pintype "passive"))
    )
    (net (code "14") (name "/row7") (class "Default")
      (node (ref "D243") (pin "2") (pinfunction "K_2") (pintype "passive"))
      (node (ref "D245") (pin "2") (pinfunction "K_2") (pintype "passive"))
      (node (ref "D247") (pin "2") (pinfunction "K_2") (pintype "passive"))
      (node (ref "D249") (pin "2") (pinfunction "K_2") (pintype "passive"))
      (node (ref "D251") (pin "2") (pinfunction "K_2") (pintype "passive"))
      (node (ref "D253") (pin "2") (pinfunction "K_2") (pintype "passive"))
      (node (ref "D255") (pin "2") (pinfunction "K_2") (pintype "passive"))
    )
    (net (code "15") (name "/row8") (class "Default")
      (node (ref "D244") (pin "2") (pinfunction "K_2") (pintype "passive"))
      (node (ref "D246") (pin "2") (pinfunction "K_2") (pintype "passive"))
      (node (ref "D248") (pin "2") (pinfunction "K_2") (pintype "passive"))
      (node (ref "D250") (pin "2") (pinfunction "K_2") (pintype "passive"))
      (node (ref "D252") (pin "2") (pinfunction "K_2") (pintype "passive"))
      (node (ref "D254") (pin "2") (pinfunction "K_2") (pintype "passive"))
      (node (ref "D256") (pin "2") (pinfunction "K_2") (pintype "passive"))
    )
    (net (code "16") (name "/row9") (class "Default")
      (node (ref "D257") (pin "2") (pinfunction "K_2") (pintype "passive"))
      (node (ref "D259") (pin "2") (pinfunction "K_2") (pintype "passive"))
      (node (ref "D261") (pin "2") (pinfunction "K_2") (pintype "passive"))
      (node (ref "D265") (pin "2") (pinfunction "K_2") (pintype "passive"))
      (node (ref "D267") (pin "2") (pinfunction "K_2") (pintype "passive"))
    )
    (net (code "17") (name "/row10") (class "Default")
      (node (ref "D258") (pin "2") (pinfunction "K_2") (pintype "passive"))
      (node (ref "D260") (pin "2") (pinfunction "K_2") (pintype "passive"))
      (node (ref "D262") (pin "2") (pinfunction "K_2") (pintype "passive"))
      (node (ref "D264") (pin "2") (pinfunction "K_2") (pintype "passive"))
      (node (ref "D266") (pin "2") (pinfunction "K_2") (pintype "passive"))
    )
    (net (code "18") (name "Net-(D201-A)") (class "Default")
      (node (ref "D201") (pin "1") (pinfunction "A_1") (pintype "passive"))
      (node (ref "S201") (pin "1") (pinfunction "1_1") (pintype "passive"))
    )
    (net (code "19") (name "Net-(D202-A)") (class "Default")
      (node (ref "D202") (pin "1") (pinfunction "A_1") (pintype "passive"))
      (node (ref "S202") (pin "1") (pinfunction "1_1") (pintype "passive"))
    )
    (net (code "20") (name "Net-(D203-A)") (class "Default")
      (node (ref "D203") (pin "1") (pinfunction "A_1") (pintype "passive"))
      (node (ref "S203") (pin "1") (pinfunction "1_1") (pintype "passive"))
    )
    (net (code "21") (name "Net-(D204-A)") (class "Default")
      (node (ref "D204") (pin "1") (pinfunction "A_1") (pintype "passive"))
      (node (ref "S204") (pin "1") (pinfunction "1_1") (pintype "passive"))
    )
    (net (code "22") (name "Net-(D205-A)") (class "Default")
      (node (ref "D205") (pin "1") (pinfunction "A_1") (pintype "passive"))
      (node (ref "S205") (pin "1") (pinfunction "1_1") (pintype "passive"))
    )
    (net (code "23") (name "Net-(D206-A)") (class "Default")
      (node (ref "D206") (pin "1") (pinfunction "A_1") (pintype "passive"))
      (node (ref "S206") (pin "1") (pinfunction "1_1") (pintype "passive"))
    )
    (net (code "24") (name "Net-(D207-A)") (class "Default")
      (node (ref "D207") (pin "1") (pinfunction "A_1") (pintype "passive"))
      (node (ref "S207") (pin "1") (pinfunction "1_1") (pintype "passive"))
    )
    (net (code "25") (name "Net-(D208-A)") (class "Default")
      (node (ref "D208") (pin "1") (pinfunction "A_1") (pintype "passive"))
      (node (ref "S208") (pin "1") (pinfunction "1_1") (pintype "passive"))
    )
    (net (code "26") (name "Net-(D209-A)") (class "Default")
      (node (ref "D209") (pin "1") (pinfunction "A_1") (pintype "passive"))
      (node (ref "S209") (pin "1") (pinfunction "1_1") (pintype "passive"))
    )
    (net (code "27") (name "Net-(D210-A)") (class "Default")
      (node (ref "D210") (pin "1") (pinfunction "A_1") (pintype "passive"))
      (node (ref "S210") (pin "1") (pinfunction "1_1") (pintype "passive"))
    )
    (net (code "28") (name "Net-(D211-A)") (class "Default")
      (node (ref "D211") (pin "1") (pinfunction "A_1") (pintype "passive"))
      (node (ref "S211") (pin "1") (pinfunction "1_1") (pintype "passive"))
    )
    (net (code "29") (name "Net-(D212-A)") (class "Default")
      (node (ref "D212") (pin "1") (pinfunction "A_1") (pintype "passive"))
      (node (ref "S212") (pin "1") (pinfunction "1_1") (pintype "passive"))
    )
    (net (code "30") (name "Net-(D213-A)") (class "Default")
      (node (ref "D213") (pin "1") (pinfunction "A_1") (pintype "passive"))
      (node (ref "S213") (pin "1") (pinfunction "1_1") (pintype "passive"))
    )
    (net (code "31") (name "Net-(D215-A)") (class "Default")
      (node (ref "D215") (pin "1") (pinfunction "A_1") (pintype "passive"))
      (node (ref "S215") (pin "1") (pinfunction "1_1") (pintype "passive"))
    )
    (net (code "32") (name "Net-(D216-A)") (class "Default")
      (node (ref "D216") (pin "1") (pinfunction "A_1") (pintype "passive"))
      (node (ref "S216") (pin "1") (pinfunction "1_1") (pintype "passive"))
    )
    (net (code "33") (name "Net-(D217-A)") (class "Default")
      (node (ref "D217") (pin "1") (pinfunction "A_1") (pintype "passive"))
      (node (ref "S217") (pin "1") (pinfunction "1_1") (pintype "passive"))
    )
    (net (code "34") (name "Net-(D218-A)") (class "Default")
      (node (ref "D218") (pin "1") (pinfunction "A_1") (pintype "passive"))
      (node (ref "S218") (pin "1") (pinfunction "1_1") (pintype "passive"))
    )
    (net (code "35") (name "Net-(D219-A)") (class "Default")
      (node (ref "D219") (pin "1") (pinfunction "A_1") (pintype "passive"))
      (node (ref "S219") (pin "1") (pinfunction "1_1") (pintype "passive"))
    )
    (net (code "36") (name "Net-(D220-A)") (class "Default")
      (node (ref "D220") (pin "1") (pinfunction "A_1") (pintype "passive"))
      (node (ref "S220") (pin "1") (pinfunction "1_1") (pintype "passive"))
    )
    (net (code "37") (name "Net-(D221-A)") (class "Default")
      (node (ref "D221") (pin "1") (pinfunction "A_1") (pintype "passive"))
      (node (ref "S221") (pin "1") (pinfunction "1_1") (pintype "passive"))
    )
    (net (code "38") (name "Net-(D222-A)") (class "Default")
      (node (ref "D222") (pin "1") (pinfunction "A_1") (pintype "passive"))
      (node (ref "S222") (pin "1") (pinfunction "1_1") (pintype "passive"))
    )
    (net (code "39") (name "Net-(D223-A)") (class "Default")
      (node (ref "D223") (pin "1") (pinfunction "A_1") (pintype "passive"))
      (node (ref "S223") (pin "1") (pinfunction "1_1") (pintype "passive"))
    )
    (net (code "40") (name "Net-(D224-A)") (class "Default")
      (node (ref "D224") (pin "1") (pinfunction "A_1") (pintype "passive"))
      (node (ref "S224") (pin "1") (pinfunction "1_1") (pintype "passive"))
    )
    (net (code "41") (name "Net-(D225-A)") (class "Default")
      (node (ref "D225") (pin "1") (pinfunction "A_1") (pintype "passive"))
      (node (ref "S225") (pin "1") (pinfunction "1_1") (pintype "passive"))
    )
    (net (code "42") (name "Net-(D226-A)") (class "Default")
      (node (ref "D226") (pin "1") (pinfunction "A_1") (pintype "passive"))
      (node (ref "S226") (pin "1") (pinfunction "1_1") (pintype "passive"))
    )
    (net (code "43") (name "Net-(D227-A)") (class "Default")
      (node (ref "D227") (pin "1") (pinfunction "A_1") (pintype "passive"))
      (node (ref "S227") (pin "1") (pinfunction "1_1") (pintype "passive"))
    )
    (net (code "44") (name "Net-(D228-A)") (class "Default")
      (node (ref "D228") (pin "1") (pinfunction "A_1") (pintype "passive"))
      (node (ref "S228") (pin "2") (pinfunction "2_2") (pintype "passive"))
    )
    (net (code "45") (name "Net-(D229-A)") (class "Default")
      (node (ref "D229") (pin "1") (pinfunction "A_1") (pintype "passive"))
      (node (ref "S229") (pin "1") (pinfunction "1_1") (pintype "passive"))
    )
    (net (code "46") (name "Net-(D230-A)") (class "Default")
      (node (ref "D230") (pin "1") (pinfunction "A_1") (pintype "passive"))
      (node (ref "S230") (pin "1") (pinfunction "1_1") (pintype "passive"))
    )
    (net (code "47") (name "Net-(D231-A)") (class "Default")
      (node (ref "D231") (pin "1") (pinfunction "A_1") (pintype "passive"))
      (node (ref "S231") (pin "1") (pinfunction "1_1") (pintype "passive"))
    )
    (net (code "48") (name "Net-(D232-A)") (class "Default")
      (node (ref "D232") (pin "1") (pinfunction "A_1") (pintype "passive"))
      (node (ref "S232") (pin "1") (pinfunction "1_1") (pintype "passive"))
    )
    (net (code "49") (name "Net-(D233-A)") (class "Default")
      (node (ref "D233") (pin "1") (pinfunction "A_1") (pintype "passive"))
      (node (ref "S233") (pin "1") (pinfunction "1_1") (pintype "passive"))
    )
    (net (code "50") (name "Net-(D234-A)") (class "Default")
      (node (ref "D234") (pin "1") (pinfunction "A_1") (pintype "passive"))
      (node (ref "S234") (pin "1") (pinfunction "1_1") (pintype "passive"))
    )
    (net (code "51") (name "Net-(D235-A)") (class "Default")
      (node (ref "D235") (pin "1") (pinfunction "A_1") (pintype "passive"))
      (node (ref "S235") (pin "1") (pinfunction "1_1") (pintype "passive"))
    )
    (net (code "52") (name "Net-(D236-A)") (class "Default")
      (node (ref "D236") (pin "1") (pinfunction "A_1") (pintype "passive"))
      (node (ref "S236") (pin "1") (pinfunction "1_1") (pintype "passive"))
    )
    (net (code "53") (name "Net-(D237-A)") (class "Default")
      (node (ref "D237") (pin "1") (pinfunction "A_1") (pintype "passive"))
      (node (ref "S237") (pin "1") (pinfunction "1_1") (pintype "passive"))
    )
    (net (code "54") (name "Net-(D238-A)") (class "Default")
      (node (ref "D238") (pin "1") (pinfunction "A_1") (pintype "passive"))
      (node (ref "S238") (pin "1") (pinfunction "1_1") (pintype "passive"))
    )
    (net (code "55") (name "Net-(D239-A)") (class "Default")
      (node (ref "D239") (pin "1") (pinfunction "A_1") (pintype "passive"))
      (node (ref "S239") (pin "1") (pinfunction "1_1") (pintype "passive"))
    )
    (net (code "56") (name "Net-(D240-A)") (class "Default")
      (node (ref "D240") (pin "1") (pinfunction "A_1") (pintype "passive"))
      (node (ref "S240") (pin "1") (pinfunction "1_1") (pintype "passive"))
    )
    (net (code "57") (name "Net-(D241-A)") (class "Default")
      (node (ref "D241") (pin "1") (pinfunction "A_1") (pintype "passive"))
      (node (ref "S241") (pin "1") (pinfunction "1_1") (pintype "passive"))
    )
    (net (code "58") (name "Net-(D243-A)") (class "Default")
      (node (ref "D243") (pin "1") (pinfunction "A_1") (pintype "passive"))
      (node (ref "S243") (pin "1") (pinfunction "1_1") (pintype "passive"))
    )
    (net (code "59") (name "Net-(D244-A)") (class "Default")
      (node (ref "D244") (pin "1") (pinfunction "A_1") (pintype "passive"))
      (node (ref "S244") (pin "1") (pinfunction "1_1") (pintype "passive"))
    )
    (net (code "60") (name "Net-(D245-A)") (class "Default")
      (node (ref "D245") (pin "1") (pinfunction "A_1") (pintype "passive"))
      (node (ref "S245") (pin "1") (pinfunction "1_1") (pintype "passive"))
    )
    (net (code "61") (name "Net-(D246-A)") (class "Default")
      (node (ref "D246") (pin "1") (pinfunction "A_1") (pintype "passive"))
      (node (ref "S246") (pin "1") (pinfunction "1_1") (pintype "passive"))
    )
    (net (code "62") (name "Net-(D247-A)") (class "Default")
      (node (ref "D247") (pin "1") (pinfunction "A_1") (pintype "passive"))
      (node (ref "S247") (pin "1") (pinfunction "1_1") (pintype "passive"))
    )
    (net (code "63") (name "Net-(D248-A)") (class "Default")
      (node (ref "D248") (pin "1") (pinfunction "A_1") (pintype "passive"))
      (node (ref "S248") (pin "1") (pinfunction "1_1") (pintype "passive"))
    )
    (net (code "64") (name "Net-(D249-A)") (class "Default")
      (node (ref "D249") (pin "1") (pinfunction "A_1") (pintype "passive"))
      (node (ref "S249") (pin "1") (pinfunction "1_1") (pintype "passive"))
    )
    (net (code "65") (name "Net-(D250-A)") (class "Default")
      (node (ref "D250") (pin "1") (pinfunction "A_1") (pintype "passive"))
      (node (ref "S250") (pin "1") (pinfunction "1_1") (pintype "passive"))
    )
    (net (code "66") (name "Net-(D251-A)") (class "Default")
      (node (ref "D251") (pin "1") (pinfunction "A_1") (pintype "passive"))
      (node (ref "S251") (pin "1") (pinfunction "1_1") (pintype "passive"))
    )
    (net (code "67") (name "Net-(D252-A)") (class "Default")
      (node (ref "D252") (pin "1") (pinfunction "A_1") (pintype "passive"))
      (node (ref "S252") (pin "1") (pinfunction "1_1") (pintype "passive"))
    )
    (net (code "68") (name "Net-(D253-A)") (class "Default")
      (node (ref "D253") (pin "1") (pinfunction "A_1") (pintype "passive"))
      (node (ref "S253") (pin "1") (pinfunction "1_1") (pintype "passive"))
    )
    (net (code "69") (name "Net-(D254-A)") (class "Default")
      (node (ref "D254") (pin "1") (pinfunction "A_1") (pintype "passive"))
      (node (ref "S254") (pin "1") (pinfunction "1_1") (pintype "passive"))
    )
    (net (code "70") (name "Net-(D255-A)") (class "Default")
      (node (ref "D255") (pin "1") (pinfunction "A_1") (pintype "passive"))
      (node (ref "S255") (pin "1") (pinfunction "1_1") (pintype "passive"))
    )
    (net (code "71") (name "Net-(D256-A)") (class "Default")
      (node (ref "D256") (pin "1") (pinfunction "A_1") (pintype "passive"))
      (node (ref "S256") (pin "1") (pinfunction "1_1") (pintype "passive"))
    )
    (net (code "72") (name "Net-(D257-A)") (class "Default")
      (node (ref "D257") (pin "1") (pinfunction "A_1") (pintype "passive"))
      (node (ref "S257") (pin "1") (pinfunction "1_1") (pintype "passive"))
    )
    (net (code "73") (name "Net-(D258-A)") (class "Default")
      (node (ref "D258") (pin "1") (pinfunction "A_1") (pintype "passive"))
      (node (ref "S258") (pin "1") (pinfunction "1_1") (pintype "passive"))
    )
    (net (code "74") (name "Net-(D259-A)") (class "Default")
      (node (ref "D259") (pin "1") (pinfunction "A_1") (pintype "passive"))
      (node (ref "S259") (pin "1") (pinfunction "1_1") (pintype "passive"))
    )
    (net (code "75") (name "Net-(D260-A)") (class "Default")
      (node (ref "D260") (pin "1") (pinfunction "A_1") (pintype "passive"))
      (node (ref "S260") (pin "1") (pinfunction "1_1") (pintype "passive"))
    )
    (net (code "76") (name "Net-(D261-A)") (class "Default")
      (node (ref "D261") (pin "1") (pinfunction "A_1") (pintype "passive"))
      (node (ref "S261") (pin "2") (pinfunction "2_2") (pintype "passive"))
    )
    (net (code "77") (name "Net-(D262-A)") (class "Default")
      (node (ref "D262") (pin "1") (pinfunction "A_1") (pintype "passive"))
      (node (ref "S262") (pin "1") (pinfunction "1_1") (pintype "passive"))
    )
    (net (code "78") (name "Net-(D264-A)") (class "Default")
      (node (ref "D264") (pin "1") (pinfunction "A_1") (pintype "passive"))
      (node (ref "S264") (pin "2") (pinfunction "2_2") (pintype "passive"))
    )
    (net (code "79") (name "Net-(D265-A)") (class "Default")
      (node (ref "D265") (pin "1") (pinfunction "A_1") (pintype "passive"))
      (node (ref "S265") (pin "1") (pinfunction "1_1") (pintype "passive"))
    )
    (net (code "80") (name "Net-(D266-A)") (class "Default")
      (node (ref "D266") (pin "1") (pinfunction "A_1") (pintype "passive"))
      (node (ref "S266") (pin "1") (pinfunction "1_1") (pintype "passive"))
    )
    (net (code "81") (name "Net-(D267-A)") (class "Default")
      (node (ref "D267") (pin "1") (pinfunction "A_1") (pintype "passive"))
      (node (ref "S267") (pin "2") (pinfunction "2_2") (pintype "passive"))
    )
  )
)
